# schematic.net
KiCad netlist of a schematic drawn in Altium Designer
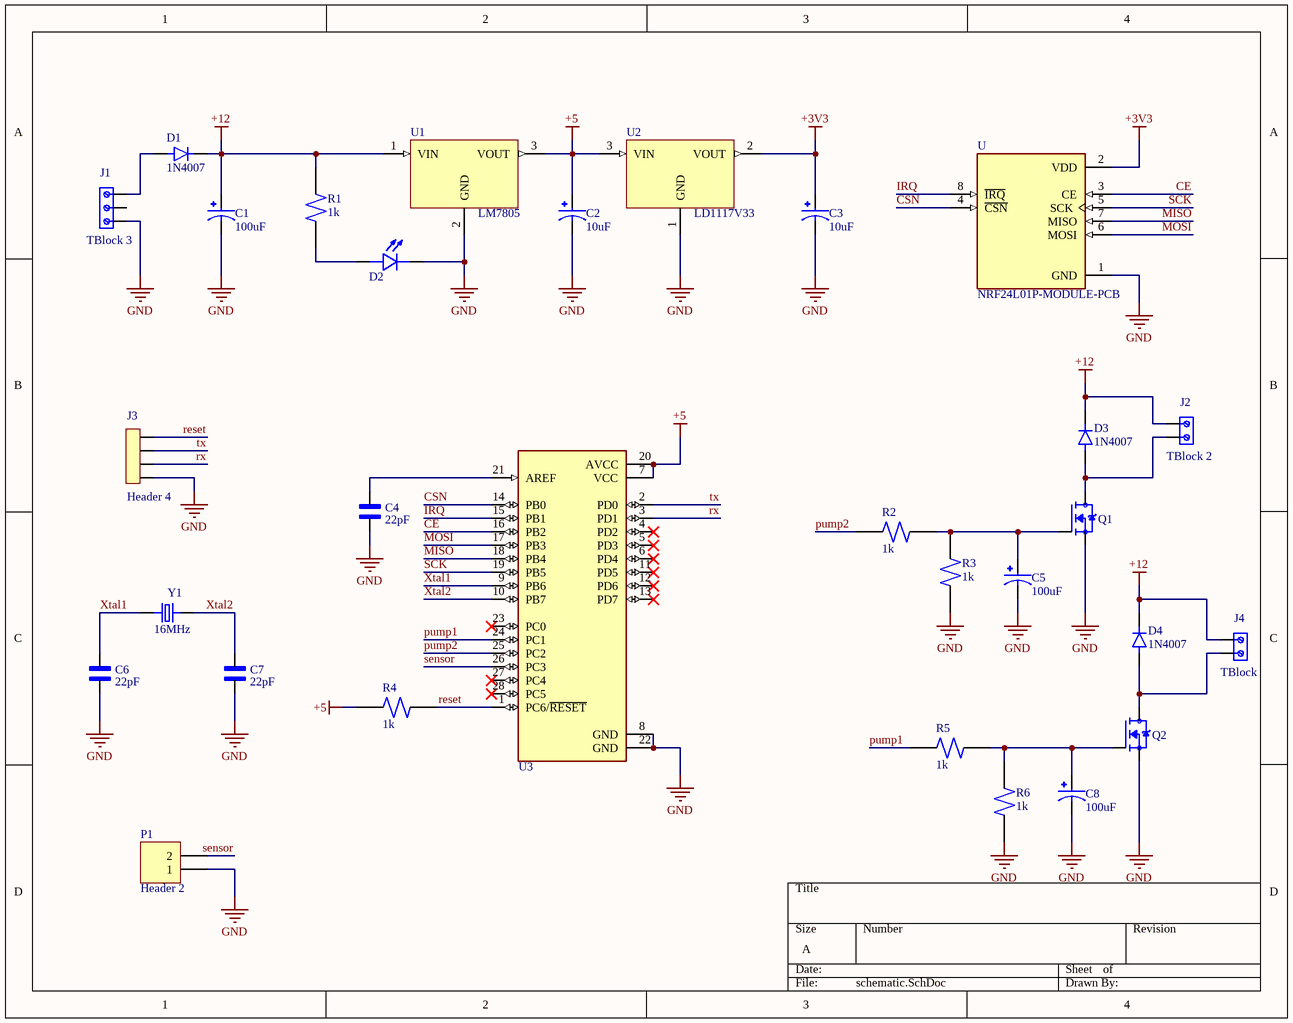
[diagram p0: schematic.SchDoc]

(export (version "E")
  (design (tool "Eeschema 10.0.6"))
  (components
    (comp (ref "C1")
      (value "100uF")
      (footprint "CAPPRD500W50D500H1100")
      (description "FS-A")
      (fields (field (name "MF") "{'manufacturer': u'Panasonic'}") (field (name "MP") "EEUFS0J221B"))
      (libsource (lib "Installed library") (part "Electrolytic capacitor"))
    )
    (comp (ref "C2")
      (value "10uF")
      (footprint "CAPPRD500W50D500H1100")
      (description "FS-A")
      (fields (field (name "MF") "{'manufacturer': u'Panasonic'}") (field (name "MP") "EEUFS0J221B"))
      (libsource (lib "Installed library") (part "Electrolytic capacitor"))
    )
    (comp (ref "C3")
      (value "10uF")
      (footprint "CAPPRD500W50D500H1100")
      (description "FS-A")
      (fields (field (name "MF") "{'manufacturer': u'Panasonic'}") (field (name "MP") "EEUFS0J221B"))
      (libsource (lib "Installed library") (part "Electrolytic capacitor"))
    )
    (comp (ref "C4")
      (value "22pF")
      (footprint "CAPRB500W50L450T300H550")
      (description "2200 pF Â±10% 250V Ceramic Capacitor X7R Radial")
      (fields (field (name "DIGI-KEY_PART_NUMBER") "445-173386-1-ND") (field (name "MF") "TDK"))
      (libsource (lib "Installed library") (part "Ceramic capacitor"))
    )
    (comp (ref "C5")
      (value "100uF")
      (footprint "CAPPRD500W50D500H1100")
      (description "FS-A")
      (fields (field (name "MF") "{'manufacturer': u'Panasonic'}") (field (name "MP") "EEUFS0J221B"))
      (libsource (lib "Installed library") (part "Electrolytic capacitor"))
    )
    (comp (ref "C6")
      (value "22pF")
      (footprint "CAPRB500W50L450T300H550")
      (description "2200 pF Â±10% 250V Ceramic Capacitor X7R Radial")
      (fields (field (name "DIGI-KEY_PART_NUMBER") "445-173386-1-ND") (field (name "MF") "TDK"))
      (libsource (lib "Installed library") (part "Ceramic capacitor"))
    )
    (comp (ref "C7")
      (value "22pF")
      (footprint "CAPRB500W50L450T300H550")
      (description "2200 pF Â±10% 250V Ceramic Capacitor X7R Radial")
      (fields (field (name "DIGI-KEY_PART_NUMBER") "445-173386-1-ND") (field (name "MF") "TDK"))
      (libsource (lib "Installed library") (part "Ceramic capacitor"))
    )
    (comp (ref "C8")
      (value "100uF")
      (footprint "CAPPRD500W50D500H1100")
      (description "FS-A")
      (fields (field (name "MF") "{'manufacturer': u'Panasonic'}") (field (name "MP") "EEUFS0J221B"))
      (libsource (lib "Installed library") (part "Electrolytic capacitor"))
    )
    (comp (ref "D1")
      (value "1N4007")
      (footprint "DIOAD1060W80L520D270")
      (description "Diode Switching 1KV 1A 2-Pin DO-41")
      (libsource (lib "Components") (part "1N4007"))
    )
    (comp (ref "D2")
      (value "L08R5000Q1")
      (footprint "LEDRD254W57D500H1070")
      (description "LED, Orange, Through Hole, T-1 3/4 (5mm), 30 mA, 2.1 V, 635 nm")
      (fields (field (name "MF") "{'manufacturer': u'LED Technology'}"))
      (libsource (lib "Installed library") (part "LED"))
    )
    (comp (ref "D3")
      (value "1N4007")
      (footprint "DIOAD1060W80L520D270")
      (description "Diode Switching 1KV 1A 2-Pin DO-41")
      (libsource (lib "Components") (part "1N4007"))
    )
    (comp (ref "D4")
      (value "1N4007")
      (footprint "DIOAD1060W80L520D270")
      (description "Diode Switching 1KV 1A 2-Pin DO-41")
      (libsource (lib "Components") (part "1N4007"))
    )
    (comp (ref "J1")
      (value "TBlock 3")
      (footprint "691214110003")
      (description "3 Position Wire to Board Terminal Block Horizontal with Board 0.138 (3.50mm) Through Hole")
      (fields (field (name "MF") "Wurth Elektronik") (field (name "MP") "691214110003"))
      (libsource (lib "Installed library") (part "Terminal blocks - 3Pins (Small)"))
    )
    (comp (ref "J2")
      (value "TBlock 2")
      (footprint "691111710002")
      (description "2 Position Wire to Board Terminal Block Horizontal with Board 0.197 _5.00mm_ Through Hole")
      (fields (field (name "MP") "691111710002") (field (name "MF") "Wurth Electronics"))
      (libsource (lib "Installed library") (part "Terminal Block - 2Pins"))
    )
    (comp (ref "J3")
      (value "Header 4")
      (footprint "SULLINS_PPTC041LFBN-RC")
      (description "4 Position Header Connector Through Hole")
      (fields (field (name "MP") "PPTC041LFBN-RC") (field (name "MF") "Sullins Connector"))
      (libsource (lib "Installed library") (part "Female header - 4Pins"))
    )
    (comp (ref "J4")
      (value "TBlock")
      (footprint "691111710002")
      (description "2 Position Wire to Board Terminal Block Horizontal with Board 0.197 _5.00mm_ Through Hole")
      (fields (field (name "MP") "691111710002") (field (name "MF") "Wurth Electronics"))
      (libsource (lib "Installed library") (part "Terminal Block - 2Pins"))
    )
    (comp (ref "P1")
      (value "Header 2")
      (footprint "HDR1X2")
      (description "Header, 2-Pin")
      (fields (field (name "PUBLISHER") "Altium Limited"))
      (libsource (lib "Miscellaneous Connectors") (part "Header 2"))
    )
    (comp (ref "Q1")
      (value "N-Channel mosfet")
      (footprint "TO254P1052X465X1989-3")
      (description "N-Channel 100V 22A (Tc) 85W (Tc) Through Hole TO-220AB")
      (fields (field (name "MP") "IRF540"))
      (libsource (lib "Installed library") (part "IRF540"))
    )
    (comp (ref "Q2")
      (value "N-Channel mosfet")
      (footprint "TO254P1052X465X1989-3")
      (description "N-Channel 100V 22A (Tc) 85W (Tc) Through Hole TO-220AB")
      (fields (field (name "MP") "IRF540"))
      (libsource (lib "Installed library") (part "IRF540"))
    )
    (comp (ref "R1")
      (value "1k")
      (footprint "RESAD1100W55L680D260")
      (description "(MFR-25FBF52-10K) 10,2 kOhm bei 1% 0,25W, 1/4W Durchbohrlochwiderstand Axial Metal Film")
      (fields (field (name "DIGI-KEY_PART_NUMBER") "10.2KXBK-ND") (field (name "MF") "Yageo"))
      (libsource (lib "Installed library") (part "Resistor (0.25W)"))
    )
    (comp (ref "R2")
      (value "1k")
      (footprint "RESAD1100W55L680D260")
      (description "(MFR-25FBF52-10K) 10,2 kOhm bei 1% 0,25W, 1/4W Durchbohrlochwiderstand Axial Metal Film")
      (fields (field (name "DIGI-KEY_PART_NUMBER") "10.2KXBK-ND") (field (name "MF") "Yageo"))
      (libsource (lib "Installed library") (part "Resistor (0.25W)"))
    )
    (comp (ref "R3")
      (value "1k")
      (footprint "RESAD1100W55L680D260")
      (description "(MFR-25FBF52-10K) 10,2 kOhm bei 1% 0,25W, 1/4W Durchbohrlochwiderstand Axial Metal Film")
      (fields (field (name "DIGI-KEY_PART_NUMBER") "10.2KXBK-ND") (field (name "MF") "Yageo"))
      (libsource (lib "Installed library") (part "Resistor (0.25W)"))
    )
    (comp (ref "R4")
      (value "1k")
      (footprint "RESAD1100W55L680D260")
      (description "(MFR-25FBF52-10K) 10,2 kOhm bei 1% 0,25W, 1/4W Durchbohrlochwiderstand Axial Metal Film")
      (fields (field (name "DIGI-KEY_PART_NUMBER") "10.2KXBK-ND") (field (name "MF") "Yageo"))
      (libsource (lib "Installed library") (part "Resistor (0.25W)"))
    )
    (comp (ref "R5")
      (value "1k")
      (footprint "RESAD1100W55L680D260")
      (description "(MFR-25FBF52-10K) 10,2 kOhm bei 1% 0,25W, 1/4W Durchbohrlochwiderstand Axial Metal Film")
      (fields (field (name "DIGI-KEY_PART_NUMBER") "10.2KXBK-ND") (field (name "MF") "Yageo"))
      (libsource (lib "Installed library") (part "Resistor (0.25W)"))
    )
    (comp (ref "R6")
      (value "1k")
      (footprint "RESAD1100W55L680D260")
      (description "(MFR-25FBF52-10K) 10,2 kOhm bei 1% 0,25W, 1/4W Durchbohrlochwiderstand Axial Metal Film")
      (fields (field (name "DIGI-KEY_PART_NUMBER") "10.2KXBK-ND") (field (name "MF") "Yageo"))
      (libsource (lib "Installed library") (part "Resistor (0.25W)"))
    )
    (comp (ref "U")
      (value "NRF24L01P-MODULE-PCB")
      (footprint "XCVR_NRF24L01P-MODULE-PCB")
      (description "- Transceiver For Use With nRF24L01+")
      (fields (field (name "MF") "Nordic Semiconductor"))
      (libsource (lib "Modules") (part "NRF24L01P-MODULE-PCB"))
    )
    (comp (ref "U1")
      (value "LM7805")
      (footprint "TO255P1020X450X1968-3")
      (fields (field (name "MP") "LM7805CT/NOPB"))
      (libsource (lib "Voltage regulator") (part "LM78__"))
    )
    (comp (ref "U2")
      (value "LD1117V33")
      (footprint "TO255P1020X450X1968-3")
      (libsource (lib "Voltage regulator") (part "LD1117V33"))
    )
    (comp (ref "U3")
      (value "ATMEGA328P-PU")
      (footprint "DIP794W46P254L2967H457Q28B")
      (description "ATmega Series 20 MHz 32 KB Flash 2 KB SRAM 8-Bit Microcontroller - DIP-28")
      (libsource (lib "Installed library") (part "ATMEGA328P-PU"))
    )
    (comp (ref "Y1")
      (value "16MHz")
      (footprint "XTAL_ECS-160-20-4X")
      (description "CRYSTAL T/H")
      (fields (field (name "MF") "{'manufacturer': u'ECS Inc.'}") (field (name "MP") "ECS-160-S-4"))
      (libsource (lib "Installed library") (part "Crystal oscilator"))
    )
  )
  (nets
    (net (code "1") (name "+3V3") (class "Default")
      (node (ref "C3") (pin "P") (pinfunction "P_P") (pintype "passive"))
      (node (ref "U") (pin "2") (pinfunction "VDD_2") (pintype "power_in"))
      (node (ref "U2") (pin "2") (pinfunction "VOUT_2") (pintype "output"))
    )
    (net (code "2") (name "+5") (class "Default")
      (node (ref "C2") (pin "P") (pinfunction "P_P") (pintype "passive"))
      (node (ref "R4") (pin "2") (pinfunction "2_2") (pintype "passive"))
      (node (ref "U1") (pin "3") (pinfunction "VOUT_3") (pintype "output"))
      (node (ref "U2") (pin "3") (pinfunction "VIN_3") (pintype "input"))
      (node (ref "U3") (pin "20") (pinfunction "AVCC_20") (pintype "power_in"))
      (node (ref "U3") (pin "7") (pinfunction "VCC_7") (pintype "power_in"))
    )
    (net (code "3") (name "+12") (class "Default")
      (node (ref "C1") (pin "P") (pinfunction "P_P") (pintype "passive"))
      (node (ref "D1") (pin "C") (pinfunction "C_C") (pintype "passive"))
      (node (ref "D3") (pin "C") (pinfunction "C_C") (pintype "passive"))
      (node (ref "D4") (pin "C") (pinfunction "C_C") (pintype "passive"))
      (node (ref "J2") (pin "1") (pinfunction "1_1") (pintype "passive"))
      (node (ref "J4") (pin "1") (pinfunction "1_1") (pintype "passive"))
      (node (ref "R1") (pin "2") (pinfunction "2_2") (pintype "passive"))
      (node (ref "U1") (pin "1") (pinfunction "VIN_1") (pintype "input"))
    )
    (net (code "4") (name "/CE") (class "Default")
      (node (ref "U") (pin "3") (pinfunction "CE_3") (pintype "input"))
      (node (ref "U3") (pin "16") (pinfunction "PB2_16") (pintype "bidirectional"))
    )
    (net (code "5") (name "/CSN") (class "Default")
      (node (ref "U") (pin "4") (pinfunction "~{CSN}_4") (pintype "input"))
      (node (ref "U3") (pin "14") (pinfunction "PB0_14") (pintype "bidirectional"))
    )
    (net (code "6") (name "/IRQ") (class "Default")
      (node (ref "U") (pin "8") (pinfunction "~{IRQ}_8") (pintype "input"))
      (node (ref "U3") (pin "15") (pinfunction "PB1_15") (pintype "bidirectional"))
    )
    (net (code "7") (name "/MISO") (class "Default")
      (node (ref "U") (pin "7") (pinfunction "MISO_7") (pintype "input"))
      (node (ref "U3") (pin "18") (pinfunction "PB4_18") (pintype "bidirectional"))
    )
    (net (code "8") (name "/MOSI") (class "Default")
      (node (ref "U") (pin "6") (pinfunction "MOSI_6") (pintype "input"))
      (node (ref "U3") (pin "17") (pinfunction "PB3_17") (pintype "bidirectional"))
    )
    (net (code "9") (name "/SCK") (class "Default")
      (node (ref "U") (pin "5") (pinfunction "SCK_5") (pintype "input"))
      (node (ref "U3") (pin "19") (pinfunction "PB5_19") (pintype "bidirectional"))
    )
    (net (code "10") (name "/Xtal1") (class "Default")
      (node (ref "C6") (pin "2") (pinfunction "2_2") (pintype "passive"))
      (node (ref "U3") (pin "9") (pinfunction "PB6_9") (pintype "bidirectional"))
      (node (ref "Y1") (pin "1") (pinfunction "1_1") (pintype "passive"))
    )
    (net (code "11") (name "/Xtal2") (class "Default")
      (node (ref "C7") (pin "2") (pinfunction "2_2") (pintype "passive"))
      (node (ref "U3") (pin "10") (pinfunction "PB7_10") (pintype "bidirectional"))
      (node (ref "Y1") (pin "2") (pinfunction "2_2") (pintype "passive"))
    )
    (net (code "12") (name "/pump1") (class "Default")
      (node (ref "R5") (pin "1") (pinfunction "1_1") (pintype "passive"))
      (node (ref "U3") (pin "24") (pinfunction "PC1_24") (pintype "bidirectional"))
    )
    (net (code "13") (name "/pump2") (class "Default")
      (node (ref "R2") (pin "1") (pinfunction "1_1") (pintype "passive"))
      (node (ref "U3") (pin "25") (pinfunction "PC2_25") (pintype "bidirectional"))
    )
    (net (code "14") (name "/reset") (class "Default")
      (node (ref "J3") (pin "1") (pinfunction "1_1") (pintype "passive"))
      (node (ref "R4") (pin "1") (pinfunction "1_1") (pintype "passive"))
      (node (ref "U3") (pin "1") (pinfunction "PC6/~{RESET}_1") (pintype "bidirectional"))
    )
    (net (code "15") (name "/rx") (class "Default")
      (node (ref "J3") (pin "3") (pinfunction "3_3") (pintype "passive"))
      (node (ref "U3") (pin "3") (pinfunction "PD1_3") (pintype "bidirectional"))
    )
    (net (code "16") (name "/sensor") (class "Default")
      (node (ref "P1") (pin "2") (pinfunction "2_2") (pintype "passive"))
      (node (ref "U3") (pin "26") (pinfunction "PC3_26") (pintype "bidirectional"))
    )
    (net (code "17") (name "/tx") (class "Default")
      (node (ref "J3") (pin "2") (pinfunction "2_2") (pintype "passive"))
      (node (ref "U3") (pin "2") (pinfunction "PD0_2") (pintype "bidirectional"))
    )
    (net (code "18") (name "GND") (class "Default")
      (node (ref "C1") (pin "N") (pinfunction "N_N") (pintype "passive"))
      (node (ref "C2") (pin "N") (pinfunction "N_N") (pintype "passive"))
      (node (ref "C3") (pin "N") (pinfunction "N_N") (pintype "passive"))
      (node (ref "C4") (pin "1") (pinfunction "1_1") (pintype "passive"))
      (node (ref "C5") (pin "N") (pinfunction "N_N") (pintype "passive"))
      (node (ref "C6") (pin "1") (pinfunction "1_1") (pintype "passive"))
      (node (ref "C7") (pin "1") (pinfunction "1_1") (pintype "passive"))
      (node (ref "C8") (pin "N") (pinfunction "N_N") (pintype "passive"))
      (node (ref "D2") (pin "C") (pinfunction "C_C") (pintype "passive"))
      (node (ref "J1") (pin "1") (pinfunction "1_1") (pintype "passive"))
      (node (ref "J3") (pin "4") (pinfunction "4_4") (pintype "passive"))
      (node (ref "P1") (pin "1") (pinfunction "1_1") (pintype "passive"))
      (node (ref "Q1") (pin "3") (pinfunction "S_3") (pintype "passive"))
      (node (ref "Q2") (pin "3") (pinfunction "S_3") (pintype "passive"))
      (node (ref "R3") (pin "2") (pinfunction "2_2") (pintype "passive"))
      (node (ref "R6") (pin "2") (pinfunction "2_2") (pintype "passive"))
      (node (ref "U") (pin "1") (pinfunction "GND_1") (pintype "power_in"))
      (node (ref "U1") (pin "2") (pinfunction "GND_2") (pintype "passive"))
      (node (ref "U2") (pin "1") (pinfunction "GND_1") (pintype "passive"))
      (node (ref "U3") (pin "22") (pinfunction "GND_22") (pintype "power_in"))
      (node (ref "U3") (pin "8") (pinfunction "GND_8") (pintype "power_in"))
    )
    (net (code "19") (name "Net-(D1-PadA)") (class "Default")
      (node (ref "D1") (pin "A") (pinfunction "A_A") (pintype "passive"))
      (node (ref "J1") (pin "3") (pinfunction "3_3") (pintype "passive"))
    )
    (net (code "20") (name "Net-(D2-PadA)") (class "Default")
      (node (ref "D2") (pin "A") (pinfunction "A_A") (pintype "passive"))
      (node (ref "R1") (pin "1") (pinfunction "1_1") (pintype "passive"))
    )
    (net (code "21") (name "Net-(Q1-D)") (class "Default")
      (node (ref "D3") (pin "A") (pinfunction "A_A") (pintype "passive"))
      (node (ref "J2") (pin "2") (pinfunction "2_2") (pintype "passive"))
      (node (ref "Q1") (pin "2") (pinfunction "D_2") (pintype "passive"))
    )
    (net (code "22") (name "Net-(Q1-G)") (class "Default")
      (node (ref "C5") (pin "P") (pinfunction "P_P") (pintype "passive"))
      (node (ref "Q1") (pin "1") (pinfunction "G_1") (pintype "passive"))
      (node (ref "R2") (pin "2") (pinfunction "2_2") (pintype "passive"))
      (node (ref "R3") (pin "1") (pinfunction "1_1") (pintype "passive"))
    )
    (net (code "23") (name "Net-(Q2-D)") (class "Default")
      (node (ref "D4") (pin "A") (pinfunction "A_A") (pintype "passive"))
      (node (ref "J4") (pin "2") (pinfunction "2_2") (pintype "passive"))
      (node (ref "Q2") (pin "2") (pinfunction "D_2") (pintype "passive"))
    )
    (net (code "24") (name "Net-(Q2-G)") (class "Default")
      (node (ref "C8") (pin "P") (pinfunction "P_P") (pintype "passive"))
      (node (ref "Q2") (pin "1") (pinfunction "G_1") (pintype "passive"))
      (node (ref "R5") (pin "2") (pinfunction "2_2") (pintype "passive"))
      (node (ref "R6") (pin "1") (pinfunction "1_1") (pintype "passive"))
    )
    (net (code "25") (name "Net-(U3-AREF)") (class "Default")
      (node (ref "C4") (pin "2") (pinfunction "2_2") (pintype "passive"))
      (node (ref "U3") (pin "21") (pinfunction "AREF_21") (pintype "input"))
    )
    (net (code "26") (name "unconnected-(J1-Pad2)") (class "Default")
      (node (ref "J1") (pin "2") (pinfunction "2_2") (pintype "passive"))
    )
    (net (code "27") (name "unconnected-(U3-PC0-Pad23)") (class "Default")
      (node (ref "U3") (pin "23") (pinfunction "PC0_23") (pintype "bidirectional+no_connect"))
    )
    (net (code "28") (name "unconnected-(U3-PC4-Pad27)") (class "Default")
      (node (ref "U3") (pin "27") (pinfunction "PC4_27") (pintype "bidirectional+no_connect"))
    )
    (net (code "29") (name "unconnected-(U3-PC5-Pad28)") (class "Default")
      (node (ref "U3") (pin "28") (pinfunction "PC5_28") (pintype "bidirectional+no_connect"))
    )
    (net (code "30") (name "unconnected-(U3-PD2-Pad4)") (class "Default")
      (node (ref "U3") (pin "4") (pinfunction "PD2_4") (pintype "bidirectional+no_connect"))
    )
    (net (code "31") (name "unconnected-(U3-PD3-Pad5)") (class "Default")
      (node (ref "U3") (pin "5") (pinfunction "PD3_5") (pintype "bidirectional+no_connect"))
    )
    (net (code "32") (name "unconnected-(U3-PD4-Pad6)") (class "Default")
      (node (ref "U3") (pin "6") (pinfunction "PD4_6") (pintype "bidirectional+no_connect"))
    )
    (net (code "33") (name "unconnected-(U3-PD5-Pad11)") (class "Default")
      (node (ref "U3") (pin "11") (pinfunction "PD5_11") (pintype "bidirectional+no_connect"))
    )
    (net (code "34") (name "unconnected-(U3-PD6-Pad12)") (class "Default")
      (node (ref "U3") (pin "12") (pinfunction "PD6_12") (pintype "bidirectional+no_connect"))
    )
    (net (code "35") (name "unconnected-(U3-PD7-Pad13)") (class "Default")
      (node (ref "U3") (pin "13") (pinfunction "PD7_13") (pintype "bidirectional+no_connect"))
    )
  )
)
